# RF.net
KiCad netlist of a schematic drawn in Altium Designer
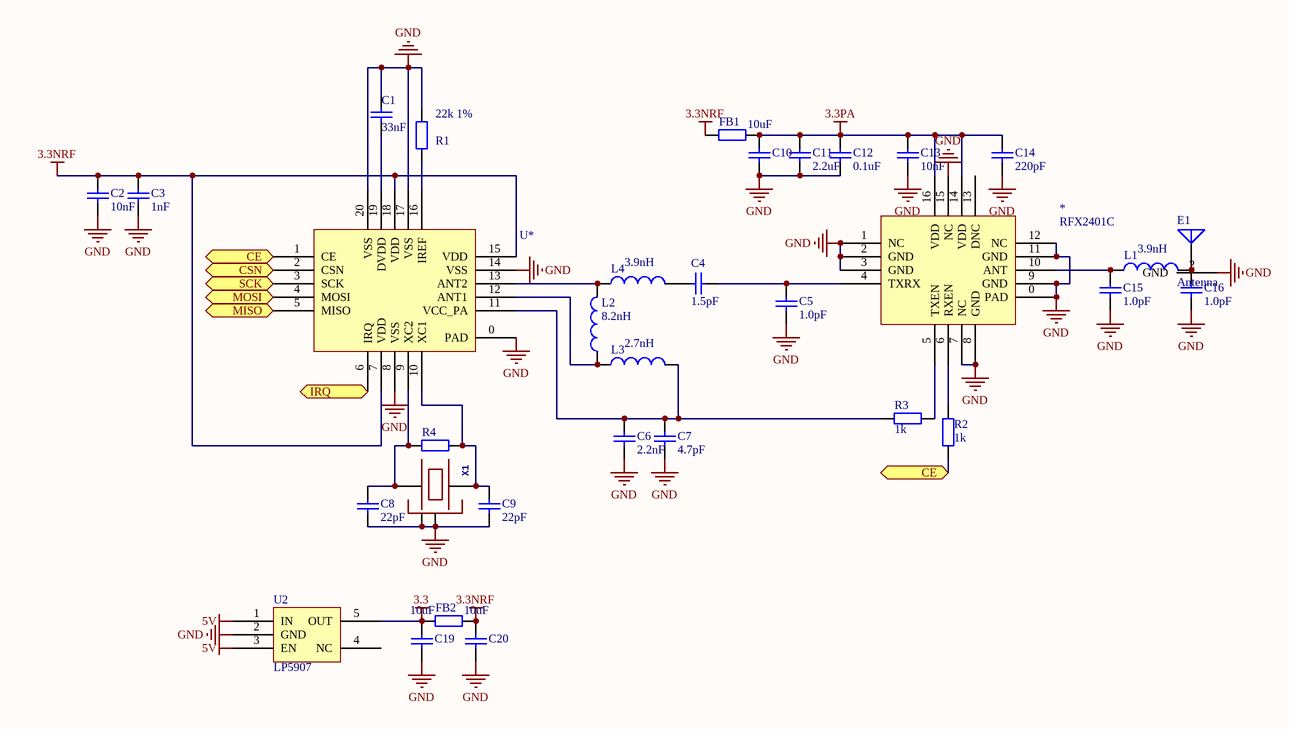
[diagram p0: RF.SchDoc]

(export (version "E")
  (design (tool "Eeschema 10.0.6"))
  (components
    (comp (ref "*")
      (value "RFX2401C")
      (footprint "RFX2401C")
      (libsource (lib "NRF24L01_PA") (part "RFX2401C"))
    )
    (comp (ref "C1")
      (value "33nF")
      (footprint "0402")
      (description "Capacitor")
      (fields (field (name "Comment") "Cap") (field (name "PUBLISHER") "Altium Limited"))
      (libsource (lib "RTC6705") (part "Cap"))
    )
    (comp (ref "C2")
      (value "10nF")
      (footprint "0402")
      (description "Capacitor")
      (fields (field (name "Comment") "Cap") (field (name "PUBLISHER") "Altium Limited"))
      (libsource (lib "RTC6705") (part "Cap"))
    )
    (comp (ref "C3")
      (value "1nF")
      (footprint "0402")
      (description "Capacitor")
      (fields (field (name "Comment") "Cap") (field (name "PUBLISHER") "Altium Limited"))
      (libsource (lib "RTC6705") (part "Cap"))
    )
    (comp (ref "C4")
      (value "1.5pF")
      (footprint "0402")
      (description "Capacitor")
      (fields (field (name "Comment") "Cap") (field (name "PUBLISHER") "Altium Limited"))
      (libsource (lib "RTC6705") (part "Cap"))
    )
    (comp (ref "C5")
      (value "1.0pF")
      (footprint "0402")
      (description "Capacitor")
      (fields (field (name "Comment") "Cap") (field (name "PUBLISHER") "Altium Limited"))
      (libsource (lib "RTC6705") (part "Cap"))
    )
    (comp (ref "C6")
      (value "2.2nF")
      (footprint "0402")
      (description "Capacitor")
      (fields (field (name "Comment") "Cap") (field (name "PUBLISHER") "Altium Limited"))
      (libsource (lib "RTC6705") (part "Cap"))
    )
    (comp (ref "C7")
      (value "4.7pF")
      (footprint "0402")
      (description "Capacitor")
      (fields (field (name "Comment") "Cap") (field (name "PUBLISHER") "Altium Limited"))
      (libsource (lib "RTC6705") (part "Cap"))
    )
    (comp (ref "C8")
      (value "22pF")
      (footprint "0402")
      (description "Capacitor")
      (fields (field (name "Comment") "Cap") (field (name "PUBLISHER") "Altium Limited"))
      (libsource (lib "RTC6705") (part "Cap"))
    )
    (comp (ref "C9")
      (value "22pF")
      (footprint "0402")
      (description "Capacitor")
      (fields (field (name "Comment") "Cap") (field (name "PUBLISHER") "Altium Limited"))
      (libsource (lib "RTC6705") (part "Cap"))
    )
    (comp (ref "C10")
      (value "10uF")
      (footprint "0603")
      (description "Capacitor")
      (fields (field (name "PUBLISHER") "Altium Limited"))
      (libsource (lib "RTC6705") (part "Cap"))
    )
    (comp (ref "C11")
      (value "2.2uF")
      (footprint "0402")
      (description "Capacitor")
      (fields (field (name "Comment") "Cap") (field (name "PUBLISHER") "Altium Limited"))
      (libsource (lib "RTC6705") (part "Cap"))
    )
    (comp (ref "C12")
      (value "0.1uF")
      (footprint "0402")
      (description "Capacitor")
      (fields (field (name "Comment") "Cap") (field (name "PUBLISHER") "Altium Limited"))
      (libsource (lib "RTC6705") (part "Cap"))
    )
    (comp (ref "C13")
      (value "10nF")
      (footprint "0402")
      (description "Capacitor")
      (fields (field (name "Comment") "Cap") (field (name "PUBLISHER") "Altium Limited"))
      (libsource (lib "RTC6705") (part "Cap"))
    )
    (comp (ref "C14")
      (value "220pF")
      (footprint "0402")
      (description "Capacitor")
      (fields (field (name "Comment") "Cap") (field (name "PUBLISHER") "Altium Limited"))
      (libsource (lib "RTC6705") (part "Cap"))
    )
    (comp (ref "C15")
      (value "1.0pF")
      (footprint "0402")
      (description "Capacitor")
      (fields (field (name "Comment") "Cap") (field (name "PUBLISHER") "Altium Limited"))
      (libsource (lib "RTC6705") (part "Cap"))
    )
    (comp (ref "C16")
      (value "1.0pF")
      (footprint "0402")
      (description "Capacitor")
      (fields (field (name "Comment") "Cap") (field (name "PUBLISHER") "Altium Limited"))
      (libsource (lib "RTC6705") (part "Cap"))
    )
    (comp (ref "C19")
      (value "10uF")
      (footprint "0603")
      (description "Capacitor")
      (fields (field (name "PUBLISHER") "Altium Limited"))
      (libsource (lib "RTC6705") (part "Cap"))
    )
    (comp (ref "C20")
      (value "10uF")
      (footprint "0603")
      (description "Capacitor")
      (fields (field (name "PUBLISHER") "Altium Limited"))
      (libsource (lib "RTC6705") (part "Cap"))
    )
    (comp (ref "E1")
      (value "Antenna")
      (footprint "IPEX")
      (description "Generic Antenna")
      (fields (field (name "PUBLISHER") "Altium Limited"))
      (libsource (lib "Miscellaneous Devices") (part "Antenna"))
    )
    (comp (ref "FB1")
      (value "FB")
      (footprint "0402")
      (description "Resistor")
      (fields (field (name "PUBLISHER") "Altium Limited"))
      (libsource (lib "") (part "Res2_1"))
    )
    (comp (ref "FB2")
      (value "FB")
      (footprint "0402")
      (description "Resistor")
      (fields (field (name "PUBLISHER") "Altium Limited"))
      (libsource (lib "") (part "Res2_1"))
    )
    (comp (ref "L1")
      (value "3.9nH")
      (footprint "0402")
      (description "Inductor")
      (fields (field (name "PUBLISHER") "Altium Limited"))
      (libsource (lib "Miscellaneous Devices") (part "Inductor"))
    )
    (comp (ref "L2")
      (value "8.2nH")
      (footprint "0402")
      (description "Inductor")
      (fields (field (name "PUBLISHER") "Altium Limited"))
      (libsource (lib "Miscellaneous Devices") (part "Inductor"))
    )
    (comp (ref "L3")
      (value "2.7nH")
      (footprint "0402")
      (description "Inductor")
      (fields (field (name "PUBLISHER") "Altium Limited"))
      (libsource (lib "Miscellaneous Devices") (part "Inductor"))
    )
    (comp (ref "L4")
      (value "3.9nH")
      (footprint "0402")
      (description "Inductor")
      (fields (field (name "PUBLISHER") "Altium Limited"))
      (libsource (lib "Miscellaneous Devices") (part "Inductor"))
    )
    (comp (ref "R1")
      (value "22k 1%")
      (footprint "0402")
      (description "Resistor")
      (fields (field (name "Comment") "Res2") (field (name "PUBLISHER") "Altium Limited"))
      (libsource (lib "") (part "Res2_2"))
    )
    (comp (ref "R2")
      (value "1k")
      (footprint "0402")
      (description "Resistor")
      (fields (field (name "Comment") "Res2") (field (name "PUBLISHER") "Altium Limited"))
      (libsource (lib "RTC6705") (part "Res2"))
    )
    (comp (ref "R3")
      (value "1k")
      (footprint "0402")
      (description "Resistor")
      (fields (field (name "Comment") "Res2") (field (name "PUBLISHER") "Altium Limited"))
      (libsource (lib "") (part "Res2_1"))
    )
    (comp (ref "R4")
      (value "1M")
      (footprint "0402")
      (description "Resistor")
      (fields (field (name "PUBLISHER") "Altium Limited"))
      (libsource (lib "") (part "Res2_1"))
    )
    (comp (ref "U*")
      (value "NRF24L01")
      (footprint "NRF24L01")
      (libsource (lib "NRF24L01_PA") (part "NRF24L01"))
    )
    (comp (ref "U2") (value "LP5907") (footprint "SOT23-5") (libsource (lib "RTC6705") (part "LP5907")))
    (comp (ref "X1")
      (value "16Mhz")
      (footprint "OSCILLATOR-3.2X2.5")
      (description "Crystal Oscillator in 3.2x2.5 SMD")
      (libsource (lib "pixhawk2") (part "OSCILLATOR-3.2X2.5"))
    )
  )
  (nets
    (net (code "1") (name "/CE") (class "Default")
      (node (ref "R2") (pin "1") (pinfunction "1_1") (pintype "passive"))
      (node (ref "U*") (pin "1") (pinfunction "CE_1") (pintype "passive"))
    )
    (net (code "2") (name "/CSN") (class "Default")
      (node (ref "U*") (pin "2") (pinfunction "CSN_2") (pintype "passive"))
    )
    (net (code "3") (name "/IRQ") (class "Default")
      (node (ref "U*") (pin "6") (pinfunction "IRQ_6") (pintype "passive"))
    )
    (net (code "4") (name "/MISO") (class "Default")
      (node (ref "U*") (pin "5") (pinfunction "MISO_5") (pintype "passive"))
    )
    (net (code "5") (name "/MOSI") (class "Default")
      (node (ref "U*") (pin "4") (pinfunction "MOSI_4") (pintype "passive"))
    )
    (net (code "6") (name "/SCK") (class "Default")
      (node (ref "U*") (pin "3") (pinfunction "SCK_3") (pintype "passive"))
    )
    (net (code "7") (name "3.3") (class "Default")
      (node (ref "C19") (pin "1") (pinfunction "1_1") (pintype "passive"))
      (node (ref "FB2") (pin "1") (pinfunction "1_1") (pintype "passive"))
      (node (ref "U2") (pin "5") (pinfunction "OUT_5") (pintype "passive"))
    )
    (net (code "8") (name "3.3NRF") (class "Default")
      (node (ref "C2") (pin "1") (pinfunction "1_1") (pintype "passive"))
      (node (ref "C20") (pin "1") (pinfunction "1_1") (pintype "passive"))
      (node (ref "C3") (pin "1") (pinfunction "1_1") (pintype "passive"))
      (node (ref "FB1") (pin "1") (pinfunction "1_1") (pintype "passive"))
      (node (ref "FB2") (pin "2") (pinfunction "2_2") (pintype "passive"))
      (node (ref "U*") (pin "15") (pinfunction "VDD_15") (pintype "passive"))
      (node (ref "U*") (pin "18") (pinfunction "VDD_18") (pintype "passive"))
      (node (ref "U*") (pin "7") (pinfunction "VDD_7") (pintype "passive"))
    )
    (net (code "9") (name "3.3PA") (class "Default")
      (node (ref "*") (pin "14") (pinfunction "VDD_14") (pintype "passive"))
      (node (ref "*") (pin "16") (pinfunction "VDD_16") (pintype "passive"))
      (node (ref "C10") (pin "1") (pinfunction "1_1") (pintype "passive"))
      (node (ref "C11") (pin "1") (pinfunction "1_1") (pintype "passive"))
      (node (ref "C12") (pin "1") (pinfunction "1_1") (pintype "passive"))
      (node (ref "C13") (pin "1") (pinfunction "1_1") (pintype "passive"))
      (node (ref "C14") (pin "1") (pinfunction "1_1") (pintype "passive"))
      (node (ref "FB1") (pin "2") (pinfunction "2_2") (pintype "passive"))
    )
    (net (code "10") (name "5V") (class "Default")
      (node (ref "U2") (pin "1") (pinfunction "IN_1") (pintype "passive"))
      (node (ref "U2") (pin "3") (pinfunction "EN_3") (pintype "passive"))
    )
    (net (code "11") (name "GND") (class "Default")
      (node (ref "*") (pin "0") (pinfunction "PAD_0") (pintype "passive"))
      (node (ref "*") (pin "1") (pinfunction "NC_1") (pintype "passive"))
      (node (ref "*") (pin "11") (pinfunction "GND_11") (pintype "passive"))
      (node (ref "*") (pin "12") (pinfunction "NC_12") (pintype "passive"))
      (node (ref "*") (pin "15") (pinfunction "NC_15") (pintype "passive"))
      (node (ref "*") (pin "2") (pinfunction "GND_2") (pintype "passive"))
      (node (ref "*") (pin "3") (pinfunction "GND_3") (pintype "passive"))
      (node (ref "*") (pin "7") (pinfunction "NC_7") (pintype "passive"))
      (node (ref "*") (pin "8") (pinfunction "GND_8") (pintype "passive"))
      (node (ref "*") (pin "9") (pinfunction "GND_9") (pintype "passive"))
      (node (ref "C1") (pin "1") (pinfunction "1_1") (pintype "passive"))
      (node (ref "C10") (pin "2") (pinfunction "2_2") (pintype "passive"))
      (node (ref "C11") (pin "2") (pinfunction "2_2") (pintype "passive"))
      (node (ref "C12") (pin "2") (pinfunction "2_2") (pintype "passive"))
      (node (ref "C13") (pin "2") (pinfunction "2_2") (pintype "passive"))
      (node (ref "C14") (pin "2") (pinfunction "2_2") (pintype "passive"))
      (node (ref "C15") (pin "2") (pinfunction "2_2") (pintype "passive"))
      (node (ref "C16") (pin "2") (pinfunction "2_2") (pintype "passive"))
      (node (ref "C19") (pin "2") (pinfunction "2_2") (pintype "passive"))
      (node (ref "C2") (pin "2") (pinfunction "2_2") (pintype "passive"))
      (node (ref "C20") (pin "2") (pinfunction "2_2") (pintype "passive"))
      (node (ref "C3") (pin "2") (pinfunction "2_2") (pintype "passive"))
      (node (ref "C5") (pin "2") (pinfunction "2_2") (pintype "passive"))
      (node (ref "C6") (pin "2") (pinfunction "2_2") (pintype "passive"))
      (node (ref "C7") (pin "2") (pinfunction "2_2") (pintype "passive"))
      (node (ref "C8") (pin "2") (pinfunction "2_2") (pintype "passive"))
      (node (ref "C9") (pin "2") (pinfunction "2_2") (pintype "passive"))
      (node (ref "E1") (pin "2") (pinfunction "GND_2") (pintype "passive"))
      (node (ref "R1") (pin "1") (pinfunction "1_1") (pintype "passive"))
      (node (ref "U*") (pin "0") (pinfunction "PAD_0") (pintype "passive"))
      (node (ref "U*") (pin "14") (pinfunction "VSS_14") (pintype "passive"))
      (node (ref "U*") (pin "17") (pinfunction "VSS_17") (pintype "passive"))
      (node (ref "U*") (pin "20") (pinfunction "VSS_20") (pintype "passive"))
      (node (ref "U*") (pin "8") (pinfunction "VSS_8") (pintype "passive"))
      (node (ref "U2") (pin "2") (pinfunction "GND_2") (pintype "passive"))
      (node (ref "X1") (pin "2") (pinfunction "NC_2_2") (pintype "open_emitter"))
      (node (ref "X1") (pin "4") (pinfunction "NC_4_4") (pintype "open_emitter"))
    )
    (net (code "12") (name "Net-(*-ANT)") (class "Default")
      (node (ref "*") (pin "10") (pinfunction "ANT_10") (pintype "passive"))
      (node (ref "C15") (pin "1") (pinfunction "1_1") (pintype "passive"))
      (node (ref "L1") (pin "1") (pinfunction "1_1") (pintype "passive"))
    )
    (net (code "13") (name "Net-(*-RXEN)") (class "Default")
      (node (ref "*") (pin "6") (pinfunction "RXEN_6") (pintype "passive"))
      (node (ref "R2") (pin "2") (pinfunction "2_2") (pintype "passive"))
    )
    (net (code "14") (name "Net-(*-TXEN)") (class "Default")
      (node (ref "*") (pin "5") (pinfunction "TXEN_5") (pintype "passive"))
      (node (ref "R3") (pin "2") (pinfunction "2_2") (pintype "passive"))
    )
    (net (code "15") (name "Net-(*-TXRX)") (class "Default")
      (node (ref "*") (pin "4") (pinfunction "TXRX_4") (pintype "passive"))
      (node (ref "C4") (pin "2") (pinfunction "2_2") (pintype "passive"))
      (node (ref "C5") (pin "1") (pinfunction "1_1") (pintype "passive"))
    )
    (net (code "16") (name "Net-(C4-Pad1)") (class "Default")
      (node (ref "C4") (pin "1") (pinfunction "1_1") (pintype "passive"))
      (node (ref "L4") (pin "2") (pinfunction "2_2") (pintype "passive"))
    )
    (net (code "17") (name "Net-(E1-ANT)") (class "Default")
      (node (ref "C16") (pin "1") (pinfunction "1_1") (pintype "passive"))
      (node (ref "E1") (pin "1") (pinfunction "ANT_1") (pintype "passive"))
      (node (ref "L1") (pin "2") (pinfunction "2_2") (pintype "passive"))
    )
    (net (code "18") (name "Net-(U*-ANT1)") (class "Default")
      (node (ref "L2") (pin "1") (pinfunction "1_1") (pintype "passive"))
      (node (ref "L3") (pin "1") (pinfunction "1_1") (pintype "passive"))
      (node (ref "U*") (pin "12") (pinfunction "ANT1_12") (pintype "passive"))
    )
    (net (code "19") (name "Net-(U*-ANT2)") (class "Default")
      (node (ref "L2") (pin "2") (pinfunction "2_2") (pintype "passive"))
      (node (ref "L4") (pin "1") (pinfunction "1_1") (pintype "passive"))
      (node (ref "U*") (pin "13") (pinfunction "ANT2_13") (pintype "passive"))
    )
    (net (code "20") (name "Net-(U*-DVDD)") (class "Default")
      (node (ref "C1") (pin "2") (pinfunction "2_2") (pintype "passive"))
      (node (ref "U*") (pin "19") (pinfunction "DVDD_19") (pintype "passive"))
    )
    (net (code "21") (name "Net-(U*-IREF)") (class "Default")
      (node (ref "R1") (pin "2") (pinfunction "2_2") (pintype "passive"))
      (node (ref "U*") (pin "16") (pinfunction "IREF_16") (pintype "passive"))
    )
    (net (code "22") (name "Net-(U*-VCC_PA)") (class "Default")
      (node (ref "C6") (pin "1") (pinfunction "1_1") (pintype "passive"))
      (node (ref "C7") (pin "1") (pinfunction "1_1") (pintype "passive"))
      (node (ref "L3") (pin "2") (pinfunction "2_2") (pintype "passive"))
      (node (ref "R3") (pin "1") (pinfunction "1_1") (pintype "passive"))
      (node (ref "U*") (pin "11") (pinfunction "VCC_PA_11") (pintype "passive"))
    )
    (net (code "23") (name "Net-(U*-XC1)") (class "Default")
      (node (ref "C9") (pin "1") (pinfunction "1_1") (pintype "passive"))
      (node (ref "R4") (pin "2") (pinfunction "2_2") (pintype "passive"))
      (node (ref "U*") (pin "10") (pinfunction "XC1_10") (pintype "passive"))
      (node (ref "X1") (pin "3") (pinfunction "3_3") (pintype "passive"))
    )
    (net (code "24") (name "Net-(U*-XC2)") (class "Default")
      (node (ref "C8") (pin "1") (pinfunction "1_1") (pintype "passive"))
      (node (ref "R4") (pin "1") (pinfunction "1_1") (pintype "passive"))
      (node (ref "U*") (pin "9") (pinfunction "XC2_9") (pintype "passive"))
      (node (ref "X1") (pin "1") (pinfunction "1_1") (pintype "passive"))
    )
    (net (code "25") (name "unconnected-(*-DNC-Pad13)") (class "Default")
      (node (ref "*") (pin "13") (pinfunction "DNC_13") (pintype "passive"))
    )
    (net (code "26") (name "unconnected-(U2-NC-Pad4)") (class "Default")
      (node (ref "U2") (pin "4") (pinfunction "NC_4") (pintype "passive"))
    )
  )
)
